# RN2483A.net
KiCad netlist of a schematic drawn in Altium Designer
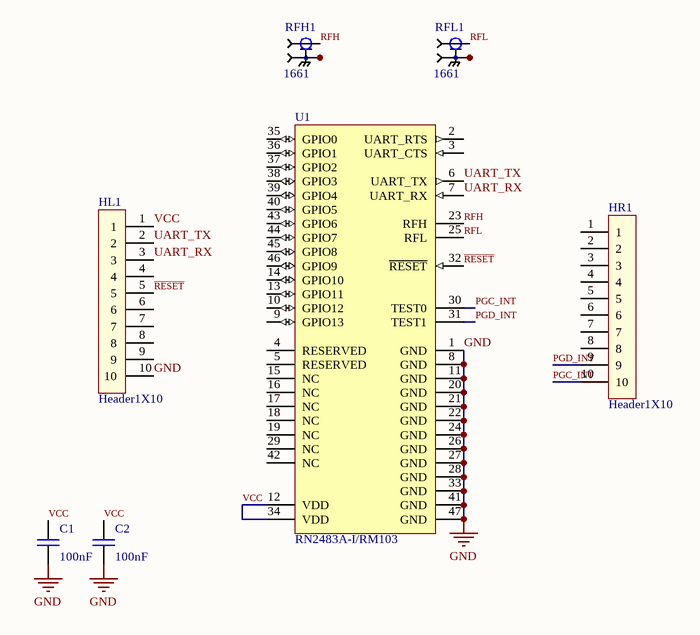
[diagram p0: RN2483A.SchDoc]

(export (version "E")
  (design (tool "Eeschema 10.0.6"))
  (components
    (comp (ref "C1")
      (value "100nF")
      (footprint "C0603")
      (description "C0603")
      (fields (field (name "Comment") "02016D104KAT2A"))
      (libsource (lib "Passive components") (part "02016D104KAT2A"))
    )
    (comp (ref "C2")
      (value "100nF")
      (footprint "C0603")
      (description "C0603")
      (fields (field (name "Comment") "02016D104KAT2A"))
      (libsource (lib "Passive components") (part "02016D104KAT2A"))
    )
    (comp (ref "HL1")
      (value "Header1X10")
      (footprint "Header1X10")
      (libsource (lib "") (part "Header1X10_1"))
    )
    (comp (ref "HR1")
      (value "Header1X10")
      (footprint "Header1X10")
      (libsource (lib "Header1X10") (part "Header1X10"))
    )
    (comp (ref "RFH1")
      (value "1661")
      (footprint "*MOLEX_1661")
      (description "uFL SMT Antenna Connector")
      (fields (field (name "MF") "Keystone Electronics"))
      (libsource (lib "1661") (part "1661"))
    )
    (comp (ref "RFL1")
      (value "1661")
      (footprint "*MOLEX_1661")
      (description "uFL SMT Antenna Connector")
      (fields (field (name "MF") "Keystone Electronics"))
      (libsource (lib "1661") (part "1661"))
    )
    (comp (ref "U1")
      (value "RN2483A-I/RM103")
      (footprint "MCHP-MODULE-47_V")
      (fields (field (name "MANUFACTURER") "Microchip"))
      (libsource (lib "Altium Content Vault") (part "MCHP-RN2483-MODULE-47"))
    )
  )
  (nets
    (net (code "1") (name "/PGC_INT") (class "Default")
      (node (ref "HR1") (pin "10") (pinfunction "10_10") (pintype "passive"))
      (node (ref "U1") (pin "30") (pinfunction "TEST0_30") (pintype "passive"))
    )
    (net (code "2") (name "/PGD_INT") (class "Default")
      (node (ref "HR1") (pin "9") (pinfunction "9_9") (pintype "passive"))
      (node (ref "U1") (pin "31") (pinfunction "TEST1_31") (pintype "passive"))
    )
    (net (code "3") (name "/RFH") (class "Default")
      (node (ref "RFH1") (pin "1") (pinfunction "SIG_1") (pintype "passive"))
      (node (ref "U1") (pin "23") (pinfunction "RFH_23") (pintype "passive"))
    )
    (net (code "4") (name "/RFL") (class "Default")
      (node (ref "RFL1") (pin "1") (pinfunction "SIG_1") (pintype "passive"))
      (node (ref "U1") (pin "25") (pinfunction "RFL_25") (pintype "passive"))
    )
    (net (code "5") (name "/UART_RX") (class "Default")
      (node (ref "HL1") (pin "3") (pinfunction "3_3") (pintype "passive"))
      (node (ref "U1") (pin "7") (pinfunction "UART_RX_7") (pintype "input"))
    )
    (net (code "6") (name "/UART_TX") (class "Default")
      (node (ref "HL1") (pin "2") (pinfunction "2_2") (pintype "passive"))
      (node (ref "U1") (pin "6") (pinfunction "UART_TX_6") (pintype "output"))
    )
    (net (code "7") (name "/VCC") (class "Default")
      (node (ref "C1") (pin "2") (pinfunction "2_2") (pintype "passive"))
      (node (ref "C2") (pin "2") (pinfunction "2_2") (pintype "passive"))
      (node (ref "HL1") (pin "1") (pinfunction "1_1") (pintype "passive"))
      (node (ref "U1") (pin "12") (pinfunction "VDD_12") (pintype "power_in"))
      (node (ref "U1") (pin "34") (pinfunction "VDD_34") (pintype "power_in"))
    )
    (net (code "8") (name "/~{RESET}") (class "Default")
      (node (ref "HL1") (pin "5") (pinfunction "5_5") (pintype "passive"))
      (node (ref "U1") (pin "32") (pinfunction "~{RESET}_32") (pintype "input"))
    )
    (net (code "9") (name "GND") (class "Default")
      (node (ref "C1") (pin "1") (pinfunction "1_1") (pintype "passive"))
      (node (ref "C2") (pin "1") (pinfunction "1_1") (pintype "passive"))
      (node (ref "HL1") (pin "10") (pinfunction "10_10") (pintype "passive"))
      (node (ref "U1") (pin "1") (pinfunction "GND_1") (pintype "power_in"))
      (node (ref "U1") (pin "11") (pinfunction "GND_11") (pintype "power_in"))
      (node (ref "U1") (pin "20") (pinfunction "GND_20") (pintype "power_in"))
      (node (ref "U1") (pin "21") (pinfunction "GND_21") (pintype "power_in"))
      (node (ref "U1") (pin "22") (pinfunction "GND_22") (pintype "power_in"))
      (node (ref "U1") (pin "24") (pinfunction "GND_24") (pintype "power_in"))
      (node (ref "U1") (pin "26") (pinfunction "GND_26") (pintype "power_in"))
      (node (ref "U1") (pin "27") (pinfunction "GND_27") (pintype "power_in"))
      (node (ref "U1") (pin "28") (pinfunction "GND_28") (pintype "power_in"))
      (node (ref "U1") (pin "33") (pinfunction "GND_33") (pintype "power_in"))
      (node (ref "U1") (pin "41") (pinfunction "GND_41") (pintype "power_in"))
      (node (ref "U1") (pin "47") (pinfunction "GND_47") (pintype "power_in"))
      (node (ref "U1") (pin "8") (pinfunction "GND_8") (pintype "power_in"))
    )
    (net (code "10") (name "Net-(RFH1-GND-Pad2)") (class "Default")
      (node (ref "RFH1") (pin "2") (pinfunction "GND_2") (pintype "passive"))
      (node (ref "RFH1") (pin "3") (pinfunction "GND_3") (pintype "passive"))
      (node (ref "RFH1") (pin "4") (pinfunction "GND_4") (pintype "passive"))
    )
    (net (code "11") (name "Net-(RFL1-GND-Pad2)") (class "Default")
      (node (ref "RFL1") (pin "2") (pinfunction "GND_2") (pintype "passive"))
      (node (ref "RFL1") (pin "3") (pinfunction "GND_3") (pintype "passive"))
      (node (ref "RFL1") (pin "4") (pinfunction "GND_4") (pintype "passive"))
    )
    (net (code "12") (name "unconnected-(HL1-Pad4)") (class "Default")
      (node (ref "HL1") (pin "4") (pinfunction "4_4") (pintype "passive"))
    )
    (net (code "13") (name "unconnected-(HL1-Pad6)") (class "Default")
      (node (ref "HL1") (pin "6") (pinfunction "6_6") (pintype "passive"))
    )
    (net (code "14") (name "unconnected-(HL1-Pad7)") (class "Default")
      (node (ref "HL1") (pin "7") (pinfunction "7_7") (pintype "passive"))
    )
    (net (code "15") (name "unconnected-(HL1-Pad8)") (class "Default")
      (node (ref "HL1") (pin "8") (pinfunction "8_8") (pintype "passive"))
    )
    (net (code "16") (name "unconnected-(HL1-Pad9)") (class "Default")
      (node (ref "HL1") (pin "9") (pinfunction "9_9") (pintype "passive"))
    )
    (net (code "17") (name "unconnected-(HR1-Pad1)") (class "Default")
      (node (ref "HR1") (pin "1") (pinfunction "1_1") (pintype "passive"))
    )
    (net (code "18") (name "unconnected-(HR1-Pad2)") (class "Default")
      (node (ref "HR1") (pin "2") (pinfunction "2_2") (pintype "passive"))
    )
    (net (code "19") (name "unconnected-(HR1-Pad3)") (class "Default")
      (node (ref "HR1") (pin "3") (pinfunction "3_3") (pintype "passive"))
    )
    (net (code "20") (name "unconnected-(HR1-Pad4)") (class "Default")
      (node (ref "HR1") (pin "4") (pinfunction "4_4") (pintype "passive"))
    )
    (net (code "21") (name "unconnected-(HR1-Pad5)") (class "Default")
      (node (ref "HR1") (pin "5") (pinfunction "5_5") (pintype "passive"))
    )
    (net (code "22") (name "unconnected-(HR1-Pad6)") (class "Default")
      (node (ref "HR1") (pin "6") (pinfunction "6_6") (pintype "passive"))
    )
    (net (code "23") (name "unconnected-(HR1-Pad7)") (class "Default")
      (node (ref "HR1") (pin "7") (pinfunction "7_7") (pintype "passive"))
    )
    (net (code "24") (name "unconnected-(HR1-Pad8)") (class "Default")
      (node (ref "HR1") (pin "8") (pinfunction "8_8") (pintype "passive"))
    )
    (net (code "25") (name "unconnected-(U1-GPIO0-Pad35)") (class "Default")
      (node (ref "U1") (pin "35") (pinfunction "GPIO0_35") (pintype "bidirectional"))
    )
    (net (code "26") (name "unconnected-(U1-GPIO1-Pad36)") (class "Default")
      (node (ref "U1") (pin "36") (pinfunction "GPIO1_36") (pintype "bidirectional"))
    )
    (net (code "27") (name "unconnected-(U1-GPIO2-Pad37)") (class "Default")
      (node (ref "U1") (pin "37") (pinfunction "GPIO2_37") (pintype "bidirectional"))
    )
    (net (code "28") (name "unconnected-(U1-GPIO3-Pad38)") (class "Default")
      (node (ref "U1") (pin "38") (pinfunction "GPIO3_38") (pintype "bidirectional"))
    )
    (net (code "29") (name "unconnected-(U1-GPIO4-Pad39)") (class "Default")
      (node (ref "U1") (pin "39") (pinfunction "GPIO4_39") (pintype "bidirectional"))
    )
    (net (code "30") (name "unconnected-(U1-GPIO5-Pad40)") (class "Default")
      (node (ref "U1") (pin "40") (pinfunction "GPIO5_40") (pintype "bidirectional"))
    )
    (net (code "31") (name "unconnected-(U1-GPIO6-Pad43)") (class "Default")
      (node (ref "U1") (pin "43") (pinfunction "GPIO6_43") (pintype "bidirectional"))
    )
    (net (code "32") (name "unconnected-(U1-GPIO7-Pad44)") (class "Default")
      (node (ref "U1") (pin "44") (pinfunction "GPIO7_44") (pintype "bidirectional"))
    )
    (net (code "33") (name "unconnected-(U1-GPIO8-Pad45)") (class "Default")
      (node (ref "U1") (pin "45") (pinfunction "GPIO8_45") (pintype "bidirectional"))
    )
    (net (code "34") (name "unconnected-(U1-GPIO9-Pad46)") (class "Default")
      (node (ref "U1") (pin "46") (pinfunction "GPIO9_46") (pintype "bidirectional"))
    )
    (net (code "35") (name "unconnected-(U1-GPIO10-Pad14)") (class "Default")
      (node (ref "U1") (pin "14") (pinfunction "GPIO10_14") (pintype "bidirectional"))
    )
    (net (code "36") (name "unconnected-(U1-GPIO11-Pad13)") (class "Default")
      (node (ref "U1") (pin "13") (pinfunction "GPIO11_13") (pintype "bidirectional"))
    )
    (net (code "37") (name "unconnected-(U1-GPIO12-Pad10)") (class "Default")
      (node (ref "U1") (pin "10") (pinfunction "GPIO12_10") (pintype "bidirectional"))
    )
    (net (code "38") (name "unconnected-(U1-GPIO13-Pad9)") (class "Default")
      (node (ref "U1") (pin "9") (pinfunction "GPIO13_9") (pintype "bidirectional"))
    )
    (net (code "39") (name "unconnected-(U1-NC-Pad15)") (class "Default")
      (node (ref "U1") (pin "15") (pinfunction "NC_15") (pintype "passive"))
    )
    (net (code "40") (name "unconnected-(U1-NC-Pad16)") (class "Default")
      (node (ref "U1") (pin "16") (pinfunction "NC_16") (pintype "passive"))
    )
    (net (code "41") (name "unconnected-(U1-NC-Pad17)") (class "Default")
      (node (ref "U1") (pin "17") (pinfunction "NC_17") (pintype "passive"))
    )
    (net (code "42") (name "unconnected-(U1-NC-Pad18)") (class "Default")
      (node (ref "U1") (pin "18") (pinfunction "NC_18") (pintype "passive"))
    )
    (net (code "43") (name "unconnected-(U1-NC-Pad19)") (class "Default")
      (node (ref "U1") (pin "19") (pinfunction "NC_19") (pintype "passive"))
    )
    (net (code "44") (name "unconnected-(U1-NC-Pad29)") (class "Default")
      (node (ref "U1") (pin "29") (pinfunction "NC_29") (pintype "passive"))
    )
    (net (code "45") (name "unconnected-(U1-NC-Pad42)") (class "Default")
      (node (ref "U1") (pin "42") (pinfunction "NC_42") (pintype "passive"))
    )
    (net (code "46") (name "unconnected-(U1-RESERVED-Pad4)") (class "Default")
      (node (ref "U1") (pin "4") (pinfunction "RESERVED_4") (pintype "passive"))
    )
    (net (code "47") (name "unconnected-(U1-RESERVED-Pad5)") (class "Default")
      (node (ref "U1") (pin "5") (pinfunction "RESERVED_5") (pintype "passive"))
    )
    (net (code "48") (name "unconnected-(U1-UART_CTS-Pad3)") (class "Default")
      (node (ref "U1") (pin "3") (pinfunction "UART_CTS_3") (pintype "input"))
    )
    (net (code "49") (name "unconnected-(U1-UART_RTS-Pad2)") (class "Default")
      (node (ref "U1") (pin "2") (pinfunction "UART_RTS_2") (pintype "output"))
    )
  )
)
